# dual_supply.net
KiCad netlist of a schematic drawn in EAGLE
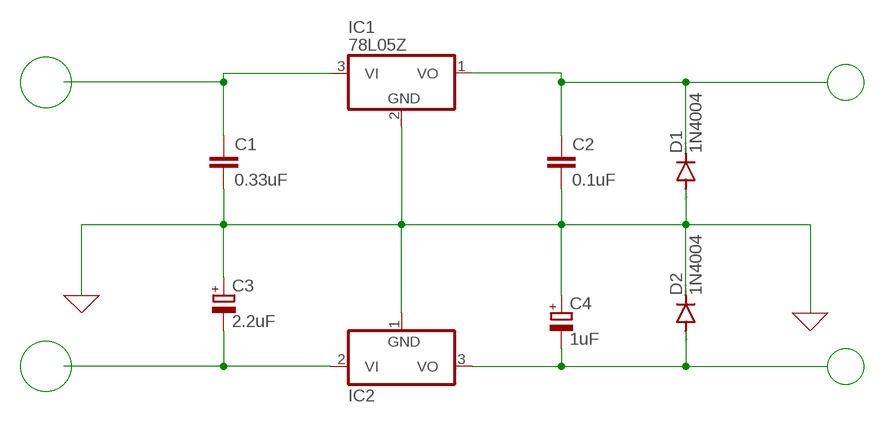
[diagram p0: schematic, sheet 1]

(export (version "E")
  (design (tool "Eeschema 10.0.6"))
  (components
    (comp (ref "C1")
      (value "0.33uF")
      (footprint "eagle-import:C2.5-3")
      (libsource (lib "eagle-import") (part "C2,5-3"))
    )
    (comp (ref "C2")
      (value "0.1uF")
      (footprint "eagle-import:C2.5-3")
      (libsource (lib "eagle-import") (part "C2,5-3"))
    )
    (comp (ref "C3")
      (value "2.2uF")
      (footprint "eagle-import:085CS_1AR")
      (libsource (lib "eagle-import") (part "CPOL-EU085CS-1AR"))
    )
    (comp (ref "C4")
      (value "1uF")
      (footprint "eagle-import:085CS_1AR")
      (libsource (lib "eagle-import") (part "CPOL-EU085CS-1AR"))
    )
    (comp (ref "D1")
      (value "1N4004")
      (footprint "eagle-import:DO41-10")
      (libsource (lib "eagle-import") (part "1N4004"))
    )
    (comp (ref "D2")
      (value "1N4004")
      (footprint "eagle-import:DO41-10")
      (libsource (lib "eagle-import") (part "1N4004"))
    )
    (comp (ref "IC1")
      (value "78L05Z")
      (footprint "eagle-import:TO92")
      (libsource (lib "eagle-import") (part "78ZL05"))
    )
    (comp (ref "IC2")
      (value "79L05Z")
      (footprint "eagle-import:TO92")
      (libsource (lib "eagle-import") (part "79ZL05"))
    )
  )
  (nets
    (net (code "1") (name "GND") (class "Default")
      (node (ref "C1") (pin "2") (pinfunction "2_2") (pintype "passive"))
      (node (ref "C2") (pin "2") (pinfunction "2_2") (pintype "passive"))
      (node (ref "C3") (pin "+") (pinfunction "+_+") (pintype "passive"))
      (node (ref "C4") (pin "+") (pinfunction "+_+") (pintype "passive"))
      (node (ref "D1") (pin "A") (pinfunction "A_A") (pintype "passive"))
      (node (ref "D2") (pin "C") (pinfunction "C_C") (pintype "passive"))
      (node (ref "IC1") (pin "2") (pinfunction "GND_2") (pintype "passive"))
      (node (ref "IC2") (pin "1") (pinfunction "GND_1") (pintype "passive"))
    )
    (net (code "2") (name "Net-(IC1-VI)") (class "Default")
      (node (ref "C1") (pin "1") (pinfunction "1_1") (pintype "passive"))
      (node (ref "IC1") (pin "3") (pinfunction "VI_3") (pintype "input"))
    )
    (net (code "3") (name "Net-(IC1-VO)") (class "Default")
      (node (ref "C2") (pin "1") (pinfunction "1_1") (pintype "passive"))
      (node (ref "D1") (pin "C") (pinfunction "C_C") (pintype "passive"))
      (node (ref "IC1") (pin "1") (pinfunction "VO_1") (pintype "passive"))
    )
    (net (code "4") (name "Net-(IC2-VI)") (class "Default")
      (node (ref "C3") (pin "-") (pinfunction "-_-") (pintype "passive"))
      (node (ref "IC2") (pin "2") (pinfunction "VI_2") (pintype "input"))
    )
    (net (code "5") (name "Net-(IC2-VO)") (class "Default")
      (node (ref "C4") (pin "-") (pinfunction "-_-") (pintype "passive"))
      (node (ref "D2") (pin "A") (pinfunction "A_A") (pintype "passive"))
      (node (ref "IC2") (pin "3") (pinfunction "VO_3") (pintype "passive"))
    )
  )
)
